# v1.net
KiCad netlist of a schematic drawn in EAGLE
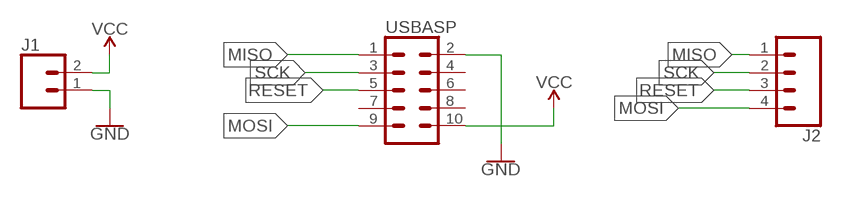
[diagram p0: schematic, sheet 1]

(export (version "E")
  (design (tool "Eeschema 10.0.6"))
  (components
    (comp (ref "J1")
      (value "CONN_02")
      (footprint "eagle-import:1X02")
      (libsource (lib "eagle-import") (part "CONN_02"))
    )
    (comp (ref "J2")
      (value "CONN_04")
      (footprint "eagle-import:1X04")
      (libsource (lib "eagle-import") (part "CONN_04"))
    )
    (comp (ref "USBASP")
      (value "CONN_05X2PTH")
      (footprint "eagle-import:2X5")
      (libsource (lib "eagle-import") (part "CONN_05X2PTH"))
    )
  )
  (nets
    (net (code "1") (name "GND") (class "Default")
      (node (ref "J1") (pin "1") (pinfunction "1_1") (pintype "passive"))
      (node (ref "USBASP") (pin "2") (pinfunction "2_2") (pintype "passive"))
    )
    (net (code "2") (name "MISO") (class "Default")
      (node (ref "J2") (pin "1") (pinfunction "1_1") (pintype "passive"))
      (node (ref "USBASP") (pin "1") (pinfunction "1_1") (pintype "passive"))
    )
    (net (code "3") (name "MOSI") (class "Default")
      (node (ref "J2") (pin "4") (pinfunction "4_4") (pintype "passive"))
      (node (ref "USBASP") (pin "9") (pinfunction "9_9") (pintype "passive"))
    )
    (net (code "4") (name "RESET") (class "Default")
      (node (ref "J2") (pin "3") (pinfunction "3_3") (pintype "passive"))
      (node (ref "USBASP") (pin "5") (pinfunction "5_5") (pintype "passive"))
    )
    (net (code "5") (name "SCK") (class "Default")
      (node (ref "J2") (pin "2") (pinfunction "2_2") (pintype "passive"))
      (node (ref "USBASP") (pin "3") (pinfunction "3_3") (pintype "passive"))
    )
    (net (code "6") (name "VCC") (class "Default")
      (node (ref "J1") (pin "2") (pinfunction "2_2") (pintype "passive"))
      (node (ref "USBASP") (pin "10") (pinfunction "10_10") (pintype "passive"))
    )
    (net (code "7") (name "unconnected-(USBASP-Pad4)") (class "Default")
      (node (ref "USBASP") (pin "4") (pinfunction "4_4") (pintype "passive"))
    )
    (net (code "8") (name "unconnected-(USBASP-Pad6)") (class "Default")
      (node (ref "USBASP") (pin "6") (pinfunction "6_6") (pintype "passive"))
    )
    (net (code "9") (name "unconnected-(USBASP-Pad7)") (class "Default")
      (node (ref "USBASP") (pin "7") (pinfunction "7_7") (pintype "passive"))
    )
    (net (code "10") (name "unconnected-(USBASP-Pad8)") (class "Default")
      (node (ref "USBASP") (pin "8") (pinfunction "8_8") (pintype "passive"))
    )
  )
)
